# Placa_final.net
KiCad netlist of a schematic drawn in EAGLE
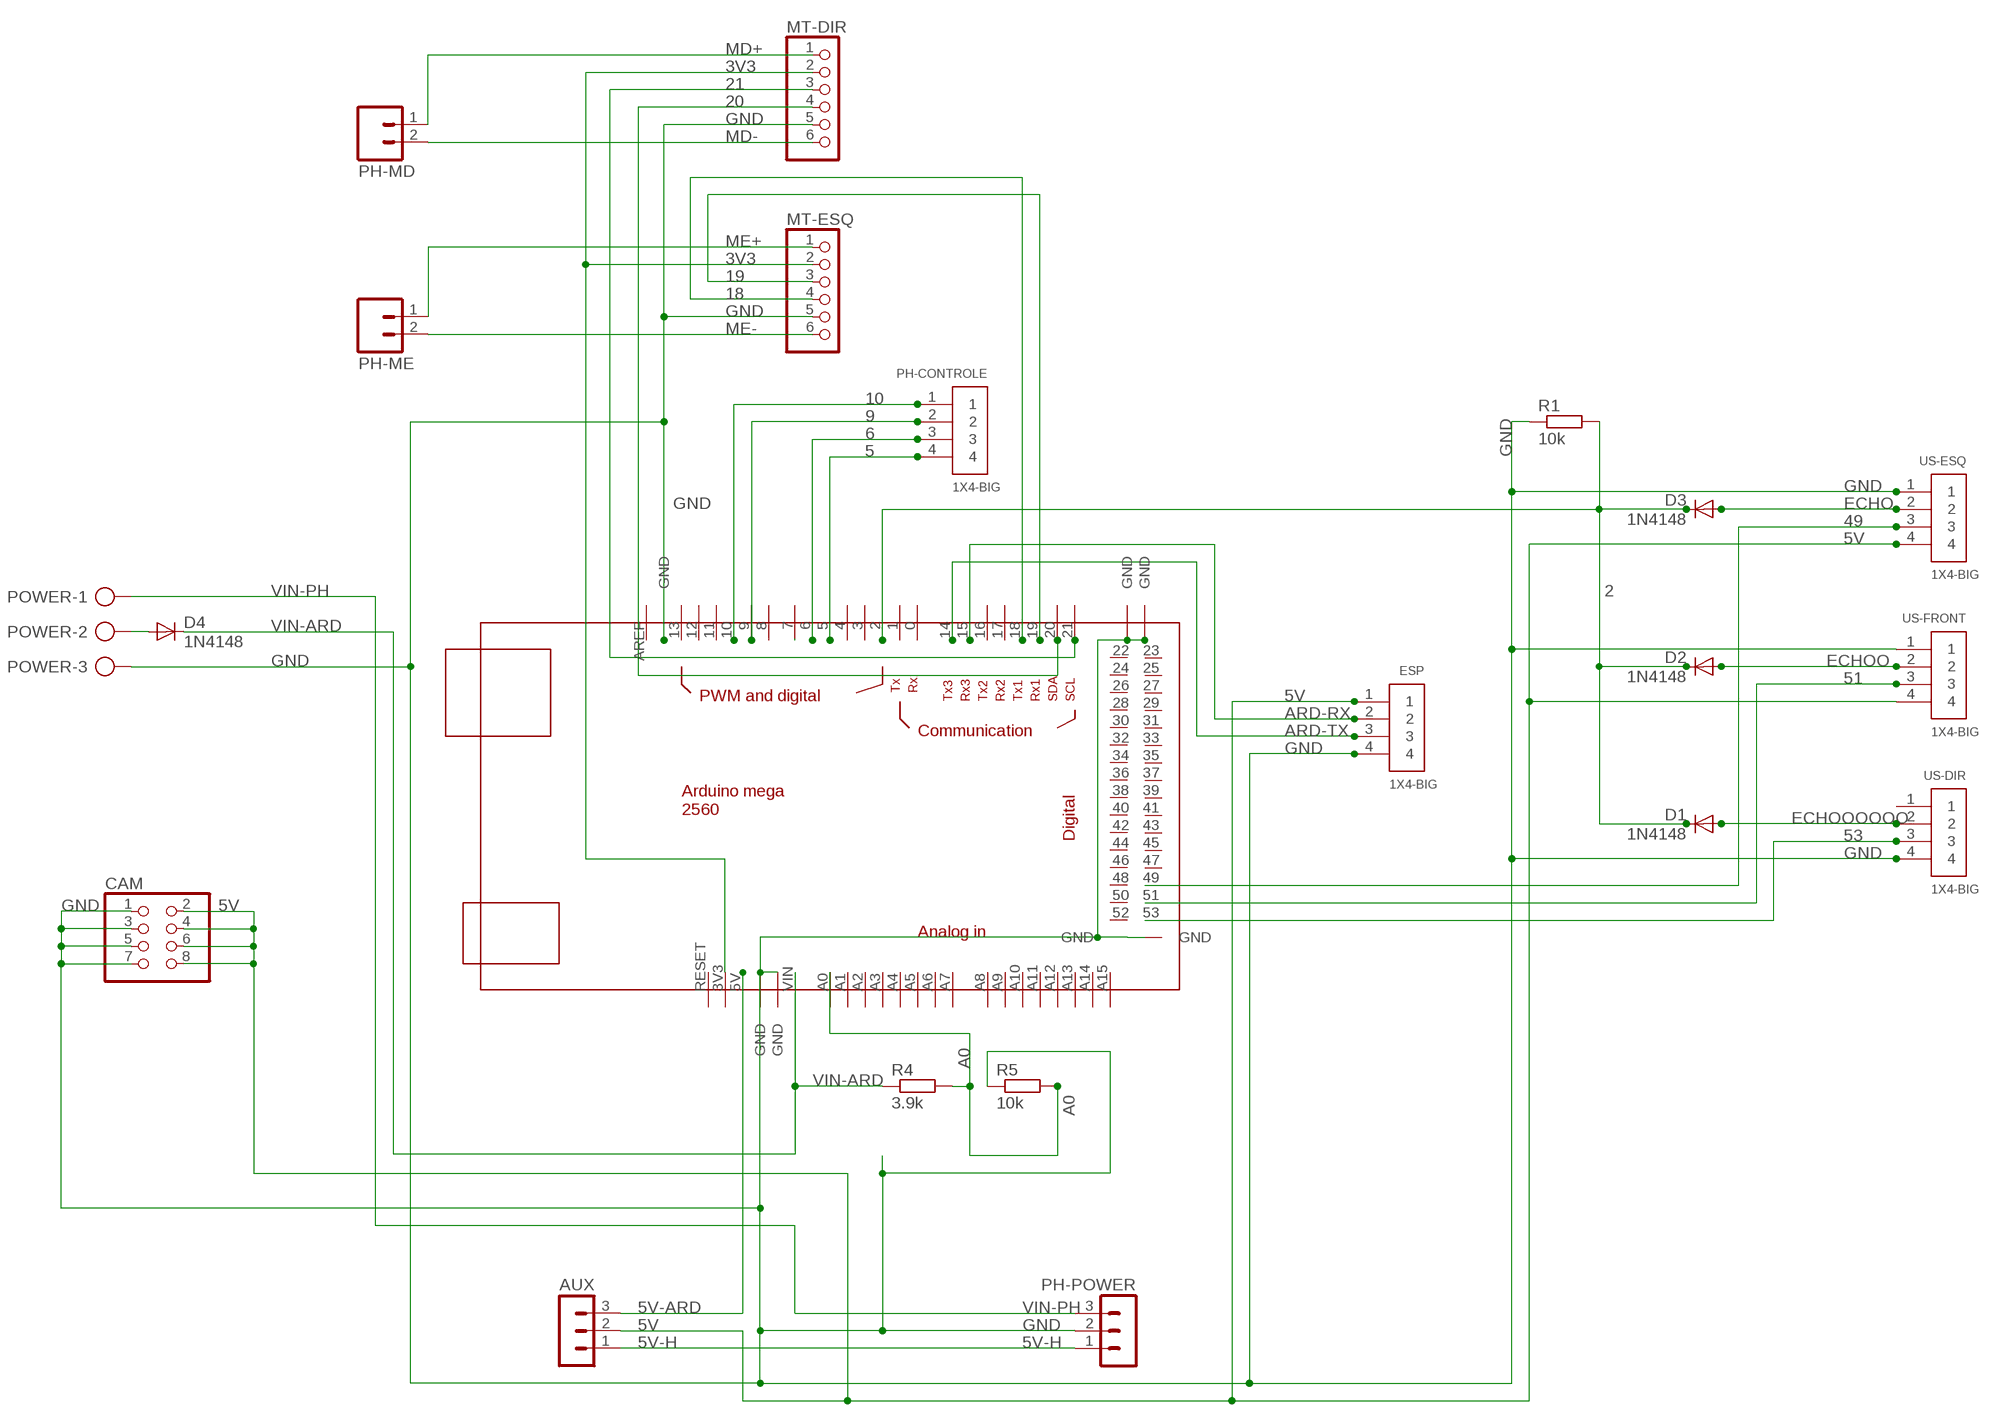
[diagram p0: schematic, sheet 1]

(export (version "E")
  (design (tool "Eeschema 10.0.6"))
  (components
    (comp (ref "AUX")
      (value "MA03-1")
      (footprint "eagle-import:MA03-1")
      (libsource (lib "eagle-import") (part "MA03-1"))
    )
    (comp (ref "CAM")
      (value "PINHD-2X4")
      (footprint "eagle-import:2X04")
      (libsource (lib "eagle-import") (part "PINHD-2X4"))
    )
    (comp (ref "D1")
      (value "1N4148")
      (footprint "eagle-import:DO35-10")
      (libsource (lib "eagle-import") (part "1N4446"))
    )
    (comp (ref "D2")
      (value "1N4148")
      (footprint "eagle-import:DO35-10")
      (libsource (lib "eagle-import") (part "1N4446"))
    )
    (comp (ref "D3")
      (value "1N4148")
      (footprint "eagle-import:DO35-10")
      (libsource (lib "eagle-import") (part "1N4446"))
    )
    (comp (ref "D4")
      (value "1N4148")
      (footprint "eagle-import:DO35-10")
      (libsource (lib "eagle-import") (part "1N4446"))
    )
    (comp (ref "ESP")
      (value "1X4-BIG")
      (footprint "eagle-import:1X04-BIG")
      (libsource (lib "eagle-import") (part "1X4-BIG"))
    )
    (comp (ref "MT-DIR")
      (value "PINHD-1X6B")
      (footprint "eagle-import:1X06-BIG")
      (libsource (lib "eagle-import") (part "PINHD-1X6B"))
    )
    (comp (ref "MT-ESQ")
      (value "PINHD-1X6B")
      (footprint "eagle-import:1X06-BIG")
      (libsource (lib "eagle-import") (part "PINHD-1X6B"))
    )
    (comp (ref "PH-CONTROLE")
      (value "1X4-BIG")
      (footprint "eagle-import:1X04-BIG")
      (libsource (lib "eagle-import") (part "1X4-BIG"))
    )
    (comp (ref "PH-MD")
      (value "M02")
      (footprint "eagle-import:02P")
      (libsource (lib "eagle-import") (part "M02"))
    )
    (comp (ref "PH-ME")
      (value "M02")
      (footprint "eagle-import:02P")
      (libsource (lib "eagle-import") (part "M02"))
    )
    (comp (ref "PH-POWER")
      (value "MA03-1")
      (footprint "eagle-import:MA03-1")
      (libsource (lib "eagle-import") (part "MA03-1"))
    )
    (comp (ref "POWER")
      (value "AK300/3")
      (footprint "eagle-import:AK300_3")
      (libsource (lib "eagle-import") (part "AK300/3"))
    )
    (comp (ref "R1")
      (value "10k")
      (footprint "eagle-import:0207_10")
      (libsource (lib "eagle-import") (part "R0207/10"))
    )
    (comp (ref "R4")
      (value "3.9k")
      (footprint "eagle-import:0207_10")
      (libsource (lib "eagle-import") (part "R0207/10"))
    )
    (comp (ref "R5")
      (value "10k")
      (footprint "eagle-import:0207_10")
      (libsource (lib "eagle-import") (part "R0207/10"))
    )
    (comp (ref "U$1")
      (value "MEGA_DEVICE")
      (footprint "eagle-import:MEGAOUTLINE")
      (libsource (lib "eagle-import") (part "MEGA_DEVICE"))
    )
    (comp (ref "US-DIR")
      (value "1X4-BIG")
      (footprint "eagle-import:1X04-BIG")
      (libsource (lib "eagle-import") (part "1X4-BIG"))
    )
    (comp (ref "US-ESQ")
      (value "1X4-BIG")
      (footprint "eagle-import:1X04-BIG")
      (libsource (lib "eagle-import") (part "1X4-BIG"))
    )
    (comp (ref "US-FRONT")
      (value "1X4-BIG")
      (footprint "eagle-import:1X04-BIG")
      (libsource (lib "eagle-import") (part "1X4-BIG"))
    )
  )
  (nets
    (net (code "1") (name "2") (class "Default")
      (node (ref "D1") (pin "C") (pinfunction "C_C") (pintype "passive"))
      (node (ref "D2") (pin "C") (pinfunction "C_C") (pintype "passive"))
      (node (ref "D3") (pin "C") (pinfunction "C_C") (pintype "passive"))
      (node (ref "R1") (pin "2") (pinfunction "2_2") (pintype "passive"))
      (node (ref "U$1") (pin "2") (pinfunction "2_2") (pintype "bidirectional"))
    )
    (net (code "2") (name "3V3") (class "Default")
      (node (ref "MT-DIR") (pin "2") (pinfunction "2_2") (pintype "passive"))
      (node (ref "MT-ESQ") (pin "2") (pinfunction "2_2") (pintype "passive"))
      (node (ref "U$1") (pin "3V3") (pinfunction "3V3_3V3") (pintype "bidirectional"))
    )
    (net (code "3") (name "5") (class "Default")
      (node (ref "PH-CONTROLE") (pin "4") (pinfunction "4_4") (pintype "bidirectional"))
      (node (ref "U$1") (pin "5") (pinfunction "5_5") (pintype "bidirectional"))
    )
    (net (code "4") (name "5V") (class "Default")
      (node (ref "AUX") (pin "2") (pinfunction "2_2") (pintype "passive"))
      (node (ref "CAM") (pin "2") (pinfunction "2_2") (pintype "passive"))
      (node (ref "CAM") (pin "4") (pinfunction "4_4") (pintype "passive"))
      (node (ref "CAM") (pin "6") (pinfunction "6_6") (pintype "passive"))
      (node (ref "CAM") (pin "8") (pinfunction "8_8") (pintype "passive"))
      (node (ref "ESP") (pin "1") (pinfunction "1_1") (pintype "bidirectional"))
      (node (ref "US-ESQ") (pin "4") (pinfunction "4_4") (pintype "bidirectional"))
      (node (ref "US-FRONT") (pin "4") (pinfunction "4_4") (pintype "bidirectional"))
    )
    (net (code "5") (name "5V-ARD") (class "Default")
      (node (ref "AUX") (pin "3") (pinfunction "3_3") (pintype "passive"))
      (node (ref "U$1") (pin "5V") (pinfunction "5V_5V") (pintype "bidirectional"))
    )
    (net (code "6") (name "5V-H") (class "Default")
      (node (ref "AUX") (pin "1") (pinfunction "1_1") (pintype "passive"))
      (node (ref "PH-POWER") (pin "1") (pinfunction "1_1") (pintype "passive"))
    )
    (net (code "7") (name "6") (class "Default")
      (node (ref "PH-CONTROLE") (pin "3") (pinfunction "3_3") (pintype "bidirectional"))
      (node (ref "U$1") (pin "6") (pinfunction "6_6") (pintype "bidirectional"))
    )
    (net (code "8") (name "9") (class "Default")
      (node (ref "PH-CONTROLE") (pin "2") (pinfunction "2_2") (pintype "bidirectional"))
      (node (ref "U$1") (pin "9") (pinfunction "9_9") (pintype "bidirectional"))
    )
    (net (code "9") (name "10") (class "Default")
      (node (ref "PH-CONTROLE") (pin "1") (pinfunction "1_1") (pintype "bidirectional"))
      (node (ref "U$1") (pin "10") (pinfunction "10_10") (pintype "bidirectional"))
    )
    (net (code "10") (name "18") (class "Default")
      (node (ref "MT-ESQ") (pin "4") (pinfunction "4_4") (pintype "passive"))
      (node (ref "U$1") (pin "18") (pinfunction "18_18") (pintype "bidirectional"))
    )
    (net (code "11") (name "19") (class "Default")
      (node (ref "MT-ESQ") (pin "3") (pinfunction "3_3") (pintype "passive"))
      (node (ref "U$1") (pin "19") (pinfunction "19_19") (pintype "bidirectional"))
    )
    (net (code "12") (name "20") (class "Default")
      (node (ref "MT-DIR") (pin "4") (pinfunction "4_4") (pintype "passive"))
      (node (ref "U$1") (pin "20") (pinfunction "20_20") (pintype "bidirectional"))
    )
    (net (code "13") (name "21") (class "Default")
      (node (ref "MT-DIR") (pin "3") (pinfunction "3_3") (pintype "passive"))
      (node (ref "U$1") (pin "21") (pinfunction "21_21") (pintype "bidirectional"))
    )
    (net (code "14") (name "49") (class "Default")
      (node (ref "U$1") (pin "49") (pinfunction "49_49") (pintype "bidirectional"))
      (node (ref "US-ESQ") (pin "3") (pinfunction "3_3") (pintype "bidirectional"))
    )
    (net (code "15") (name "51") (class "Default")
      (node (ref "U$1") (pin "51") (pinfunction "51_51") (pintype "bidirectional"))
      (node (ref "US-FRONT") (pin "3") (pinfunction "3_3") (pintype "bidirectional"))
    )
    (net (code "16") (name "53") (class "Default")
      (node (ref "U$1") (pin "53") (pinfunction "53_53") (pintype "bidirectional"))
      (node (ref "US-DIR") (pin "3") (pinfunction "3_3") (pintype "bidirectional"))
    )
    (net (code "17") (name "A0") (class "Default")
      (node (ref "R4") (pin "2") (pinfunction "2_2") (pintype "passive"))
      (node (ref "R5") (pin "2") (pinfunction "2_2") (pintype "passive"))
      (node (ref "U$1") (pin "A0") (pinfunction "A0_A0") (pintype "bidirectional"))
    )
    (net (code "18") (name "ARD-RX") (class "Default")
      (node (ref "ESP") (pin "2") (pinfunction "2_2") (pintype "bidirectional"))
      (node (ref "U$1") (pin "15") (pinfunction "15_15") (pintype "bidirectional"))
    )
    (net (code "19") (name "ARD-TX") (class "Default")
      (node (ref "ESP") (pin "3") (pinfunction "3_3") (pintype "bidirectional"))
      (node (ref "U$1") (pin "14") (pinfunction "14_14") (pintype "bidirectional"))
    )
    (net (code "20") (name "ECHO") (class "Default")
      (node (ref "D3") (pin "A") (pinfunction "A_A") (pintype "passive"))
      (node (ref "US-ESQ") (pin "2") (pinfunction "2_2") (pintype "bidirectional"))
    )
    (net (code "21") (name "ECHOO") (class "Default")
      (node (ref "D2") (pin "A") (pinfunction "A_A") (pintype "passive"))
      (node (ref "US-FRONT") (pin "2") (pinfunction "2_2") (pintype "bidirectional"))
    )
    (net (code "22") (name "ECHOOOOOO") (class "Default")
      (node (ref "D1") (pin "A") (pinfunction "A_A") (pintype "passive"))
      (node (ref "US-DIR") (pin "2") (pinfunction "2_2") (pintype "bidirectional"))
    )
    (net (code "23") (name "GND") (class "Default")
      (node (ref "CAM") (pin "1") (pinfunction "1_1") (pintype "passive"))
      (node (ref "CAM") (pin "3") (pinfunction "3_3") (pintype "passive"))
      (node (ref "CAM") (pin "5") (pinfunction "5_5") (pintype "passive"))
      (node (ref "CAM") (pin "7") (pinfunction "7_7") (pintype "passive"))
      (node (ref "ESP") (pin "4") (pinfunction "4_4") (pintype "bidirectional"))
      (node (ref "MT-DIR") (pin "5") (pinfunction "5_5") (pintype "passive"))
      (node (ref "MT-ESQ") (pin "5") (pinfunction "5_5") (pintype "passive"))
      (node (ref "PH-POWER") (pin "2") (pinfunction "2_2") (pintype "passive"))
      (node (ref "POWER") (pin "3") (pinfunction "KL_3") (pintype "passive"))
      (node (ref "R1") (pin "1") (pinfunction "1_1") (pintype "passive"))
      (node (ref "R5") (pin "1") (pinfunction "1_1") (pintype "passive"))
      (node (ref "U$1") (pin "GND@1") (pinfunction "GND_GND@1") (pintype "bidirectional"))
      (node (ref "U$1") (pin "GND@2") (pinfunction "GND_GND@2") (pintype "bidirectional"))
      (node (ref "U$1") (pin "GND@3") (pinfunction "GND_GND@3") (pintype "bidirectional"))
      (node (ref "U$1") (pin "GND@4") (pinfunction "GND_GND@4") (pintype "bidirectional"))
      (node (ref "U$1") (pin "GND@5") (pinfunction "GND_GND@5") (pintype "bidirectional"))
      (node (ref "U$1") (pin "GND@6") (pinfunction "GND_GND@6") (pintype "bidirectional"))
      (node (ref "U$1") (pin "GND@7") (pinfunction "GND_GND@7") (pintype "bidirectional"))
      (node (ref "US-DIR") (pin "4") (pinfunction "4_4") (pintype "bidirectional"))
      (node (ref "US-ESQ") (pin "1") (pinfunction "1_1") (pintype "bidirectional"))
      (node (ref "US-FRONT") (pin "1") (pinfunction "1_1") (pintype "bidirectional"))
    )
    (net (code "24") (name "MD+") (class "Default")
      (node (ref "MT-DIR") (pin "1") (pinfunction "1_1") (pintype "passive"))
      (node (ref "PH-MD") (pin "1") (pinfunction "1_1") (pintype "passive"))
    )
    (net (code "25") (name "MD-") (class "Default")
      (node (ref "MT-DIR") (pin "6") (pinfunction "6_6") (pintype "passive"))
      (node (ref "PH-MD") (pin "2") (pinfunction "2_2") (pintype "passive"))
    )
    (net (code "26") (name "ME+") (class "Default")
      (node (ref "MT-ESQ") (pin "1") (pinfunction "1_1") (pintype "passive"))
      (node (ref "PH-ME") (pin "1") (pinfunction "1_1") (pintype "passive"))
    )
    (net (code "27") (name "ME-") (class "Default")
      (node (ref "MT-ESQ") (pin "6") (pinfunction "6_6") (pintype "passive"))
      (node (ref "PH-ME") (pin "2") (pinfunction "2_2") (pintype "passive"))
    )
    (net (code "28") (name "Net-(POWERB-KL)") (class "Default")
      (node (ref "D4") (pin "A") (pinfunction "A_A") (pintype "passive"))
      (node (ref "POWER") (pin "2") (pinfunction "KL_2") (pintype "passive"))
    )
    (net (code "29") (name "VIN-ARD") (class "Default")
      (node (ref "D4") (pin "C") (pinfunction "C_C") (pintype "passive"))
      (node (ref "R4") (pin "1") (pinfunction "1_1") (pintype "passive"))
      (node (ref "U$1") (pin "VIN") (pinfunction "VIN_VIN") (pintype "bidirectional"))
    )
    (net (code "30") (name "VIN-PH") (class "Default")
      (node (ref "PH-POWER") (pin "3") (pinfunction "3_3") (pintype "passive"))
      (node (ref "POWER") (pin "1") (pinfunction "KL_1") (pintype "passive"))
    )
    (net (code "31") (name "unconnected-(U$1-Pad0)") (class "Default")
      (node (ref "U$1") (pin "0") (pinfunction "0_0") (pintype "bidirectional"))
    )
    (net (code "32") (name "unconnected-(U$1-Pad1)") (class "Default")
      (node (ref "U$1") (pin "1") (pinfunction "1_1") (pintype "bidirectional"))
    )
    (net (code "33") (name "unconnected-(U$1-Pad3)") (class "Default")
      (node (ref "U$1") (pin "3") (pinfunction "3_3") (pintype "bidirectional"))
    )
    (net (code "34") (name "unconnected-(U$1-Pad4)") (class "Default")
      (node (ref "U$1") (pin "4") (pinfunction "4_4") (pintype "bidirectional"))
    )
    (net (code "35") (name "unconnected-(U$1-Pad7)") (class "Default")
      (node (ref "U$1") (pin "7") (pinfunction "7_7") (pintype "bidirectional"))
    )
    (net (code "36") (name "unconnected-(U$1-Pad8)") (class "Default")
      (node (ref "U$1") (pin "8") (pinfunction "8_8") (pintype "bidirectional"))
    )
    (net (code "37") (name "unconnected-(U$1-Pad11)") (class "Default")
      (node (ref "U$1") (pin "11") (pinfunction "11_11") (pintype "bidirectional"))
    )
    (net (code "38") (name "unconnected-(U$1-Pad12)") (class "Default")
      (node (ref "U$1") (pin "12") (pinfunction "12_12") (pintype "bidirectional"))
    )
    (net (code "39") (name "unconnected-(U$1-Pad13)") (class "Default")
      (node (ref "U$1") (pin "13") (pinfunction "13_13") (pintype "bidirectional"))
    )
    (net (code "40") (name "unconnected-(U$1-Pad16)") (class "Default")
      (node (ref "U$1") (pin "16") (pinfunction "16_16") (pintype "bidirectional"))
    )
    (net (code "41") (name "unconnected-(U$1-Pad17)") (class "Default")
      (node (ref "U$1") (pin "17") (pinfunction "17_17") (pintype "bidirectional"))
    )
    (net (code "42") (name "unconnected-(U$1-Pad22)") (class "Default")
      (node (ref "U$1") (pin "22") (pinfunction "22_22") (pintype "bidirectional"))
    )
    (net (code "43") (name "unconnected-(U$1-Pad23)") (class "Default")
      (node (ref "U$1") (pin "23") (pinfunction "23_23") (pintype "bidirectional"))
    )
    (net (code "44") (name "unconnected-(U$1-Pad24)") (class "Default")
      (node (ref "U$1") (pin "24") (pinfunction "24_24") (pintype "bidirectional"))
    )
    (net (code "45") (name "unconnected-(U$1-Pad25)") (class "Default")
      (node (ref "U$1") (pin "25") (pinfunction "25_25") (pintype "bidirectional"))
    )
    (net (code "46") (name "unconnected-(U$1-Pad26)") (class "Default")
      (node (ref "U$1") (pin "26") (pinfunction "26_26") (pintype "bidirectional"))
    )
    (net (code "47") (name "unconnected-(U$1-Pad27)") (class "Default")
      (node (ref "U$1") (pin "27") (pinfunction "27_27") (pintype "bidirectional"))
    )
    (net (code "48") (name "unconnected-(U$1-Pad28)") (class "Default")
      (node (ref "U$1") (pin "28") (pinfunction "28_28") (pintype "bidirectional"))
    )
    (net (code "49") (name "unconnected-(U$1-Pad29)") (class "Default")
      (node (ref "U$1") (pin "29") (pinfunction "29_29") (pintype "bidirectional"))
    )
    (net (code "50") (name "unconnected-(U$1-Pad30)") (class "Default")
      (node (ref "U$1") (pin "30") (pinfunction "30_30") (pintype "bidirectional"))
    )
    (net (code "51") (name "unconnected-(U$1-Pad31)") (class "Default")
      (node (ref "U$1") (pin "31") (pinfunction "31_31") (pintype "bidirectional"))
    )
    (net (code "52") (name "unconnected-(U$1-Pad32)") (class "Default")
      (node (ref "U$1") (pin "32") (pinfunction "32_32") (pintype "bidirectional"))
    )
    (net (code "53") (name "unconnected-(U$1-Pad33)") (class "Default")
      (node (ref "U$1") (pin "33") (pinfunction "33_33") (pintype "bidirectional"))
    )
    (net (code "54") (name "unconnected-(U$1-Pad34)") (class "Default")
      (node (ref "U$1") (pin "34") (pinfunction "34_34") (pintype "bidirectional"))
    )
    (net (code "55") (name "unconnected-(U$1-Pad35)") (class "Default")
      (node (ref "U$1") (pin "35") (pinfunction "35_35") (pintype "bidirectional"))
    )
    (net (code "56") (name "unconnected-(U$1-Pad36)") (class "Default")
      (node (ref "U$1") (pin "36") (pinfunction "36_36") (pintype "bidirectional"))
    )
    (net (code "57") (name "unconnected-(U$1-Pad37)") (class "Default")
      (node (ref "U$1") (pin "37") (pinfunction "37_37") (pintype "bidirectional"))
    )
    (net (code "58") (name "unconnected-(U$1-Pad38)") (class "Default")
      (node (ref "U$1") (pin "38") (pinfunction "38_38") (pintype "bidirectional"))
    )
    (net (code "59") (name "unconnected-(U$1-Pad39)") (class "Default")
      (node (ref "U$1") (pin "39") (pinfunction "39_39") (pintype "bidirectional"))
    )
    (net (code "60") (name "unconnected-(U$1-Pad40)") (class "Default")
      (node (ref "U$1") (pin "40") (pinfunction "40_40") (pintype "bidirectional"))
    )
    (net (code "61") (name "unconnected-(U$1-Pad41)") (class "Default")
      (node (ref "U$1") (pin "41") (pinfunction "41_41") (pintype "bidirectional"))
    )
    (net (code "62") (name "unconnected-(U$1-Pad42)") (class "Default")
      (node (ref "U$1") (pin "42") (pinfunction "42_42") (pintype "bidirectional"))
    )
    (net (code "63") (name "unconnected-(U$1-Pad43)") (class "Default")
      (node (ref "U$1") (pin "43") (pinfunction "43_43") (pintype "bidirectional"))
    )
    (net (code "64") (name "unconnected-(U$1-Pad44)") (class "Default")
      (node (ref "U$1") (pin "44") (pinfunction "44_44") (pintype "bidirectional"))
    )
    (net (code "65") (name "unconnected-(U$1-Pad45)") (class "Default")
      (node (ref "U$1") (pin "45") (pinfunction "45_45") (pintype "bidirectional"))
    )
    (net (code "66") (name "unconnected-(U$1-Pad46)") (class "Default")
      (node (ref "U$1") (pin "46") (pinfunction "46_46") (pintype "bidirectional"))
    )
    (net (code "67") (name "unconnected-(U$1-Pad47)") (class "Default")
      (node (ref "U$1") (pin "47") (pinfunction "47_47") (pintype "bidirectional"))
    )
    (net (code "68") (name "unconnected-(U$1-Pad48)") (class "Default")
      (node (ref "U$1") (pin "48") (pinfunction "48_48") (pintype "bidirectional"))
    )
    (net (code "69") (name "unconnected-(U$1-Pad50)") (class "Default")
      (node (ref "U$1") (pin "50") (pinfunction "50_50") (pintype "bidirectional"))
    )
    (net (code "70") (name "unconnected-(U$1-Pad52)") (class "Default")
      (node (ref "U$1") (pin "52") (pinfunction "52_52") (pintype "bidirectional"))
    )
    (net (code "71") (name "unconnected-(U$1-PadA1)") (class "Default")
      (node (ref "U$1") (pin "A1") (pinfunction "A1_A1") (pintype "bidirectional"))
    )
    (net (code "72") (name "unconnected-(U$1-PadA2)") (class "Default")
      (node (ref "U$1") (pin "A2") (pinfunction "A2_A2") (pintype "bidirectional"))
    )
    (net (code "73") (name "unconnected-(U$1-PadA3)") (class "Default")
      (node (ref "U$1") (pin "A3") (pinfunction "A3_A3") (pintype "bidirectional"))
    )
    (net (code "74") (name "unconnected-(U$1-PadA4)") (class "Default")
      (node (ref "U$1") (pin "A4") (pinfunction "A4_A4") (pintype "bidirectional"))
    )
    (net (code "75") (name "unconnected-(U$1-PadA5)") (class "Default")
      (node (ref "U$1") (pin "A5") (pinfunction "A5_A5") (pintype "bidirectional"))
    )
    (net (code "76") (name "unconnected-(U$1-PadA6)") (class "Default")
      (node (ref "U$1") (pin "A6") (pinfunction "A6_A6") (pintype "bidirectional"))
    )
    (net (code "77") (name "unconnected-(U$1-PadA7)") (class "Default")
      (node (ref "U$1") (pin "A7") (pinfunction "A7_A7") (pintype "bidirectional"))
    )
    (net (code "78") (name "unconnected-(U$1-PadA8)") (class "Default")
      (node (ref "U$1") (pin "A8") (pinfunction "A8_A8") (pintype "bidirectional"))
    )
    (net (code "79") (name "unconnected-(U$1-PadA9)") (class "Default")
      (node (ref "U$1") (pin "A9") (pinfunction "A9_A9") (pintype "bidirectional"))
    )
    (net (code "80") (name "unconnected-(U$1-PadA10)") (class "Default")
      (node (ref "U$1") (pin "A10") (pinfunction "A10_A10") (pintype "bidirectional"))
    )
    (net (code "81") (name "unconnected-(U$1-PadA11)") (class "Default")
      (node (ref "U$1") (pin "A11") (pinfunction "A11_A11") (pintype "bidirectional"))
    )
    (net (code "82") (name "unconnected-(U$1-PadA12)") (class "Default")
      (node (ref "U$1") (pin "A12") (pinfunction "A12_A12") (pintype "bidirectional"))
    )
    (net (code "83") (name "unconnected-(U$1-PadA13)") (class "Default")
      (node (ref "U$1") (pin "A13") (pinfunction "A13_A13") (pintype "bidirectional"))
    )
    (net (code "84") (name "unconnected-(U$1-PadA14)") (class "Default")
      (node (ref "U$1") (pin "A14") (pinfunction "A14_A14") (pintype "bidirectional"))
    )
    (net (code "85") (name "unconnected-(U$1-PadA15)") (class "Default")
      (node (ref "U$1") (pin "A15") (pinfunction "A15_A15") (pintype "bidirectional"))
    )
    (net (code "86") (name "unconnected-(U$1-PadAREF)") (class "Default")
      (node (ref "U$1") (pin "AREF") (pinfunction "AREF_AREF") (pintype "bidirectional"))
    )
    (net (code "87") (name "unconnected-(U$1-PadRESET)") (class "Default")
      (node (ref "U$1") (pin "RESET") (pinfunction "RESET_RESET") (pintype "bidirectional"))
    )
    (net (code "88") (name "unconnected-(US-DIR-Pad1)") (class "Default")
      (node (ref "US-DIR") (pin "1") (pinfunction "1_1") (pintype "bidirectional"))
    )
  )
)
